# untitled.net
KiCad netlist of a schematic drawn in EAGLE
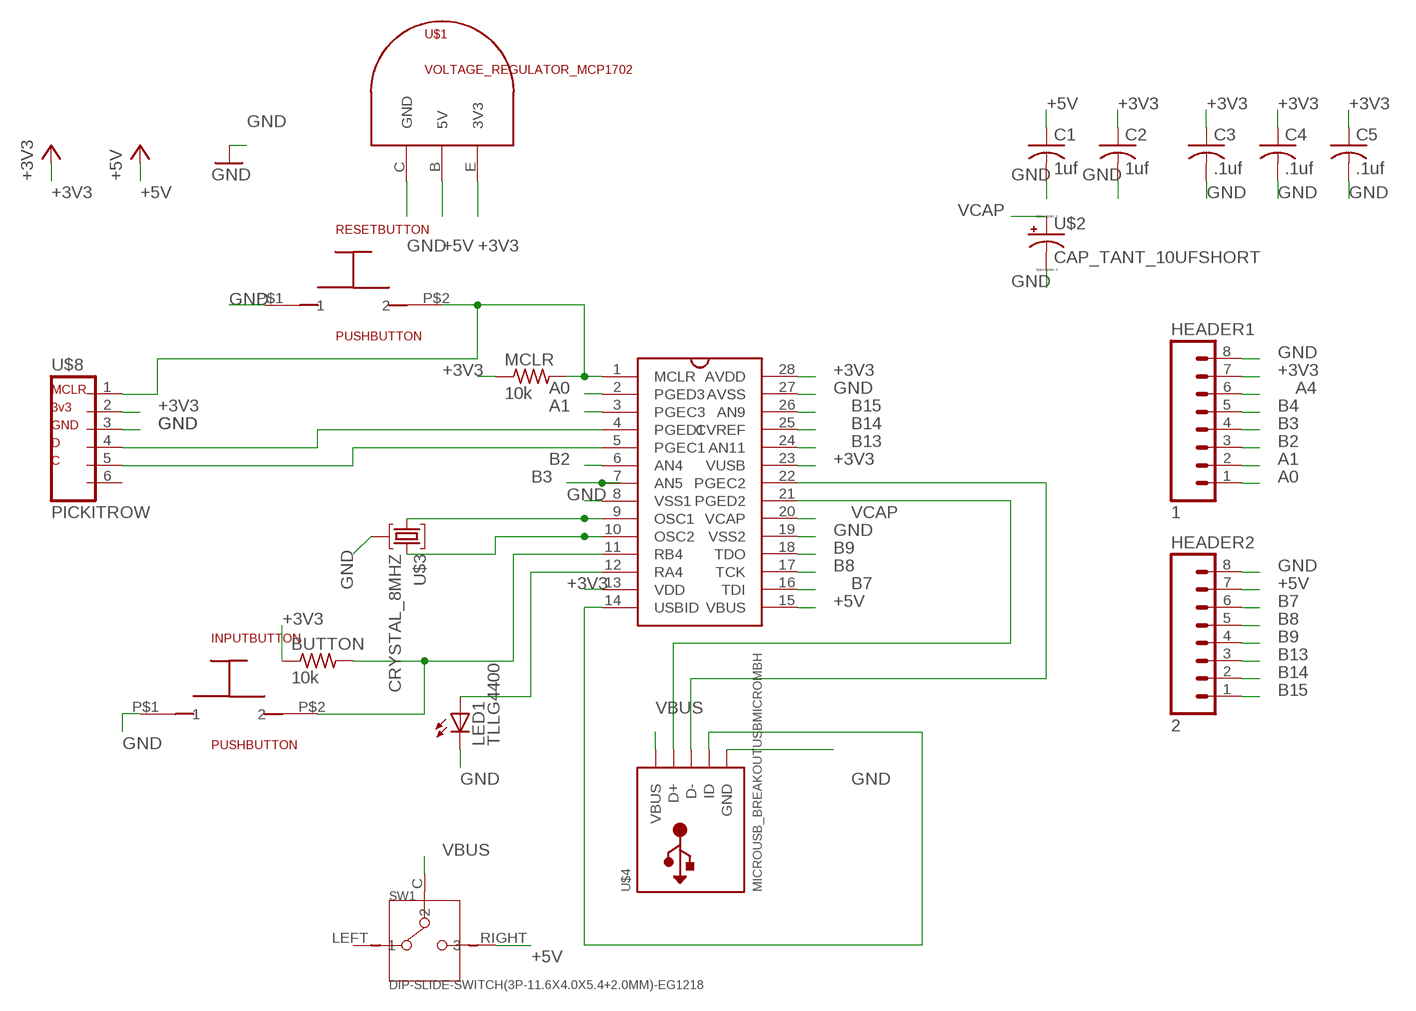
[diagram p0: schematic, sheet 1]

(export (version "E")
  (design (tool "Eeschema 10.0.6"))
  (components
    (comp (ref "BUTTON")
      (value "10k")
      (footprint "eagle-import:0207_10")
      (libsource (lib "eagle-import") (part "R-US_0207/10"))
    )
    (comp (ref "C1")
      (value "1uf")
      (footprint "eagle-import:C025-030X050")
      (libsource (lib "eagle-import") (part "C-US025-030X050"))
    )
    (comp (ref "C2")
      (value "1uf")
      (footprint "eagle-import:C025-030X050")
      (libsource (lib "eagle-import") (part "C-US025-030X050"))
    )
    (comp (ref "C3")
      (value ".1uf")
      (footprint "eagle-import:C050-030X075")
      (libsource (lib "eagle-import") (part "C-US050-030X075"))
    )
    (comp (ref "C4")
      (value ".1uf")
      (footprint "eagle-import:C025-030X050")
      (libsource (lib "eagle-import") (part "C-US025-030X050"))
    )
    (comp (ref "C5")
      (value ".1uf")
      (footprint "eagle-import:C025-030X050")
      (libsource (lib "eagle-import") (part "C-US025-030X050"))
    )
    (comp (ref "HEADER1")
      (value "1")
      (footprint "eagle-import:1X08_ROUND")
      (libsource (lib "eagle-import") (part "M08"))
    )
    (comp (ref "HEADER2")
      (value "2")
      (footprint "eagle-import:1X08_ROUND")
      (libsource (lib "eagle-import") (part "M08"))
    )
    (comp (ref "INPUTBUTTON")
      (value "PUSHBUTTON")
      (footprint "eagle-import:PUSHBUTTON")
      (libsource (lib "eagle-import") (part "PUSHBUTTON"))
    )
    (comp (ref "LED1")
      (value "TLLG4400")
      (footprint "eagle-import:LED3MM")
      (fields (field (name "MF") "VISHAY SEMICONDUCTOR"))
      (libsource (lib "eagle-import") (part "TLLG4400"))
    )
    (comp (ref "MCLR")
      (value "10k")
      (footprint "eagle-import:0207_10")
      (libsource (lib "eagle-import") (part "R-US_0207/10"))
    )
    (comp (ref "RESETBUTTON")
      (value "PUSHBUTTON")
      (footprint "eagle-import:PUSHBUTTON")
      (libsource (lib "eagle-import") (part "PUSHBUTTON"))
    )
    (comp (ref "SW1")
      (value "DIP-SLIDE-SWITCH(3P-11.6X4.0X5.4+2.0MM)-EG1218")
      (footprint "eagle-import:SW3-2.5-11.6X4.0X5.4+2.0MM")
      (libsource (lib "eagle-import") (part "DIP-SLIDE-SWITCH(3P-11.6X4.0X5.4+2.0MM)-EG1218"))
    )
    (comp (ref "U$1")
      (value "VOLTAGE_REGULATOR_MCP1702")
      (footprint "eagle-import:TO92-EBC")
      (libsource (lib "eagle-import") (part "VOLTAGE_REGULATOR_MCP1702"))
    )
    (comp (ref "U$2")
      (value "CAP_TANT_10UFSHORT")
      (footprint "eagle-import:C025-040X050POL")
      (libsource (lib "eagle-import") (part "CAP_TANT_10UFSHORT"))
    )
    (comp (ref "U$3")
      (value "CRYSTAL_8MHZ")
      (footprint "eagle-import:CRYSTAL_8MHZ")
      (libsource (lib "eagle-import") (part "CRYSTAL_8MHZ"))
    )
    (comp (ref "U$4")
      (value "MICROUSB_BREAKOUTUSBMICROMBH")
      (footprint "eagle-import:USB-MB-H")
      (libsource (lib "eagle-import") (part "MICROUSB_BREAKOUTUSBMICROMBH"))
    )
    (comp (ref "U$5")
      (value "PIC32MX250F128B")
      (footprint "eagle-import:DIL28-3")
      (libsource (lib "eagle-import") (part "PIC32MX250F128B"))
    )
    (comp (ref "U$8")
      (value "PICKITROW")
      (footprint "eagle-import:1X06_LOCK")
      (libsource (lib "eagle-import") (part "PICKITROW"))
    )
  )
  (nets
    (net (code "1") (name "+3V3") (class "Default")
      (node (ref "BUTTON") (pin "1") (pinfunction "1_1") (pintype "passive"))
      (node (ref "C2") (pin "1") (pinfunction "1_1") (pintype "passive"))
      (node (ref "C3") (pin "1") (pinfunction "1_1") (pintype "passive"))
      (node (ref "C4") (pin "1") (pinfunction "1_1") (pintype "passive"))
      (node (ref "C5") (pin "1") (pinfunction "1_1") (pintype "passive"))
      (node (ref "HEADER1") (pin "7") (pinfunction "7_7") (pintype "passive"))
      (node (ref "MCLR") (pin "1") (pinfunction "1_1") (pintype "passive"))
      (node (ref "U$1") (pin "E") (pinfunction "3V3_E") (pintype "bidirectional"))
      (node (ref "U$5") (pin "13") (pinfunction "VDD_13") (pintype "bidirectional"))
      (node (ref "U$5") (pin "23") (pinfunction "VUSB_23") (pintype "bidirectional"))
      (node (ref "U$5") (pin "28") (pinfunction "AVDD_28") (pintype "bidirectional"))
      (node (ref "U$8") (pin "2") (pinfunction "3V3_2") (pintype "passive"))
    )
    (net (code "2") (name "+5V") (class "Default")
      (node (ref "C1") (pin "1") (pinfunction "1_1") (pintype "passive"))
      (node (ref "HEADER2") (pin "7") (pinfunction "7_7") (pintype "passive"))
      (node (ref "SW1") (pin "RIGHT") (pinfunction "3_RIGHT") (pintype "bidirectional"))
      (node (ref "U$1") (pin "B") (pinfunction "5V_B") (pintype "bidirectional"))
      (node (ref "U$5") (pin "15") (pinfunction "VBUS_15") (pintype "bidirectional"))
    )
    (net (code "3") (name "/A0") (class "Default")
      (node (ref "HEADER1") (pin "1") (pinfunction "1_1") (pintype "passive"))
      (node (ref "U$5") (pin "2") (pinfunction "PGED3_2") (pintype "bidirectional"))
    )
    (net (code "4") (name "/A1") (class "Default")
      (node (ref "HEADER1") (pin "2") (pinfunction "2_2") (pintype "passive"))
      (node (ref "U$5") (pin "3") (pinfunction "PGEC3_3") (pintype "bidirectional"))
    )
    (net (code "5") (name "/A4") (class "Default")
      (node (ref "HEADER1") (pin "6") (pinfunction "6_6") (pintype "passive"))
      (node (ref "LED1") (pin "A") (pinfunction "A_A") (pintype "passive"))
      (node (ref "U$5") (pin "12") (pinfunction "RA4_12") (pintype "bidirectional"))
    )
    (net (code "6") (name "/B2") (class "Default")
      (node (ref "HEADER1") (pin "3") (pinfunction "3_3") (pintype "passive"))
      (node (ref "U$5") (pin "6") (pinfunction "AN4_6") (pintype "bidirectional"))
    )
    (net (code "7") (name "/B3") (class "Default")
      (node (ref "HEADER1") (pin "4") (pinfunction "4_4") (pintype "passive"))
      (node (ref "U$5") (pin "7") (pinfunction "AN5_7") (pintype "bidirectional"))
    )
    (net (code "8") (name "/B4") (class "Default")
      (node (ref "BUTTON") (pin "2") (pinfunction "2_2") (pintype "passive"))
      (node (ref "HEADER1") (pin "5") (pinfunction "5_5") (pintype "passive"))
      (node (ref "INPUTBUTTON") (pin "P$2") (pinfunction "2_P$2") (pintype "bidirectional"))
      (node (ref "U$5") (pin "11") (pinfunction "RB4_11") (pintype "bidirectional"))
    )
    (net (code "9") (name "/B7") (class "Default")
      (node (ref "HEADER2") (pin "6") (pinfunction "6_6") (pintype "passive"))
      (node (ref "U$5") (pin "16") (pinfunction "TDI_16") (pintype "bidirectional"))
    )
    (net (code "10") (name "/B8") (class "Default")
      (node (ref "HEADER2") (pin "5") (pinfunction "5_5") (pintype "passive"))
      (node (ref "U$5") (pin "17") (pinfunction "TCK_17") (pintype "bidirectional"))
    )
    (net (code "11") (name "/B9") (class "Default")
      (node (ref "HEADER2") (pin "4") (pinfunction "4_4") (pintype "passive"))
      (node (ref "U$5") (pin "18") (pinfunction "TDO_18") (pintype "bidirectional"))
    )
    (net (code "12") (name "/B13") (class "Default")
      (node (ref "HEADER2") (pin "3") (pinfunction "3_3") (pintype "passive"))
      (node (ref "U$5") (pin "24") (pinfunction "AN11_24") (pintype "bidirectional"))
    )
    (net (code "13") (name "/B14") (class "Default")
      (node (ref "HEADER2") (pin "2") (pinfunction "2_2") (pintype "passive"))
      (node (ref "U$5") (pin "25") (pinfunction "CVREF_25") (pintype "bidirectional"))
    )
    (net (code "14") (name "/B15") (class "Default")
      (node (ref "HEADER2") (pin "1") (pinfunction "1_1") (pintype "passive"))
      (node (ref "U$5") (pin "26") (pinfunction "AN9_26") (pintype "bidirectional"))
    )
    (net (code "15") (name "/VBUS") (class "Default")
      (node (ref "SW1") (pin "C") (pinfunction "2_C") (pintype "bidirectional"))
      (node (ref "U$4") (pin "VBUS") (pinfunction "VBUS_VBUS") (pintype "power_in"))
    )
    (net (code "16") (name "/VCAP") (class "Default")
      (node (ref "U$2") (pin "+") (pinfunction "+_+") (pintype "passive"))
      (node (ref "U$5") (pin "20") (pinfunction "VCAP_20") (pintype "bidirectional"))
    )
    (net (code "17") (name "GND") (class "Default")
      (node (ref "C1") (pin "2") (pinfunction "2_2") (pintype "passive"))
      (node (ref "C2") (pin "2") (pinfunction "2_2") (pintype "passive"))
      (node (ref "C3") (pin "2") (pinfunction "2_2") (pintype "passive"))
      (node (ref "C4") (pin "2") (pinfunction "2_2") (pintype "passive"))
      (node (ref "C5") (pin "2") (pinfunction "2_2") (pintype "passive"))
      (node (ref "HEADER1") (pin "8") (pinfunction "8_8") (pintype "passive"))
      (node (ref "HEADER2") (pin "8") (pinfunction "8_8") (pintype "passive"))
      (node (ref "INPUTBUTTON") (pin "P$1") (pinfunction "1_P$1") (pintype "bidirectional"))
      (node (ref "LED1") (pin "K") (pinfunction "C_K") (pintype "passive"))
      (node (ref "RESETBUTTON") (pin "P$1") (pinfunction "1_P$1") (pintype "bidirectional"))
      (node (ref "U$1") (pin "C") (pinfunction "GND_C") (pintype "bidirectional"))
      (node (ref "U$2") (pin "-") (pinfunction "-_-") (pintype "passive"))
      (node (ref "U$3") (pin "GND") (pinfunction "2_GND") (pintype "passive"))
      (node (ref "U$4") (pin "GND") (pinfunction "GND_GND") (pintype "power_in"))
      (node (ref "U$5") (pin "19") (pinfunction "VSS2_19") (pintype "bidirectional"))
      (node (ref "U$5") (pin "27") (pinfunction "AVSS_27") (pintype "bidirectional"))
      (node (ref "U$5") (pin "8") (pinfunction "VSS1_8") (pintype "bidirectional"))
      (node (ref "U$8") (pin "3") (pinfunction "GND_3") (pintype "passive"))
    )
    (net (code "18") (name "Net-(RESETBUTTON-2)") (class "Default")
      (node (ref "MCLR") (pin "2") (pinfunction "2_2") (pintype "passive"))
      (node (ref "RESETBUTTON") (pin "P$2") (pinfunction "2_P$2") (pintype "bidirectional"))
      (node (ref "U$5") (pin "1") (pinfunction "MCLR_1") (pintype "bidirectional"))
      (node (ref "U$8") (pin "1") (pinfunction "MCLR_1") (pintype "passive"))
    )
    (net (code "19") (name "Net-(U$3-1)") (class "Default")
      (node (ref "U$3") (pin "OSC1") (pinfunction "1_OSC1") (pintype "passive"))
      (node (ref "U$5") (pin "9") (pinfunction "OSC1_9") (pintype "bidirectional"))
    )
    (net (code "20") (name "Net-(U$3-3)") (class "Default")
      (node (ref "U$3") (pin "OSC2") (pinfunction "3_OSC2") (pintype "passive"))
      (node (ref "U$5") (pin "10") (pinfunction "OSC2_10") (pintype "bidirectional"))
    )
    (net (code "21") (name "Net-(U$5-PGEC1)") (class "Default")
      (node (ref "U$5") (pin "5") (pinfunction "PGEC1_5") (pintype "bidirectional"))
      (node (ref "U$8") (pin "5") (pinfunction "C_5") (pintype "passive"))
    )
    (net (code "22") (name "Net-(U$5-PGEC2)") (class "Default")
      (node (ref "U$4") (pin "D-") (pinfunction "D-_D-") (pintype "bidirectional"))
      (node (ref "U$5") (pin "22") (pinfunction "PGEC2_22") (pintype "bidirectional"))
    )
    (net (code "23") (name "Net-(U$5-PGED1)") (class "Default")
      (node (ref "U$5") (pin "4") (pinfunction "PGED1_4") (pintype "bidirectional"))
      (node (ref "U$8") (pin "4") (pinfunction "D_4") (pintype "passive"))
    )
    (net (code "24") (name "Net-(U$5-PGED2)") (class "Default")
      (node (ref "U$4") (pin "D+") (pinfunction "D+_D+") (pintype "bidirectional"))
      (node (ref "U$5") (pin "21") (pinfunction "PGED2_21") (pintype "bidirectional"))
    )
    (net (code "25") (name "Net-(U$5-USBID)") (class "Default")
      (node (ref "U$4") (pin "ID") (pinfunction "ID_ID") (pintype "bidirectional"))
      (node (ref "U$5") (pin "14") (pinfunction "USBID_14") (pintype "bidirectional"))
    )
    (net (code "26") (name "unconnected-(SW1-1-PadLEFT)") (class "Default")
      (node (ref "SW1") (pin "LEFT") (pinfunction "1_LEFT") (pintype "bidirectional"))
    )
    (net (code "27") (name "unconnected-(U$8-1-Pad6)") (class "Default")
      (node (ref "U$8") (pin "6") (pinfunction "1_6") (pintype "passive"))
    )
  )
)
